# XMOS_TSBOARD_PHY.net
KiCad netlist of a schematic drawn in Altium Designer
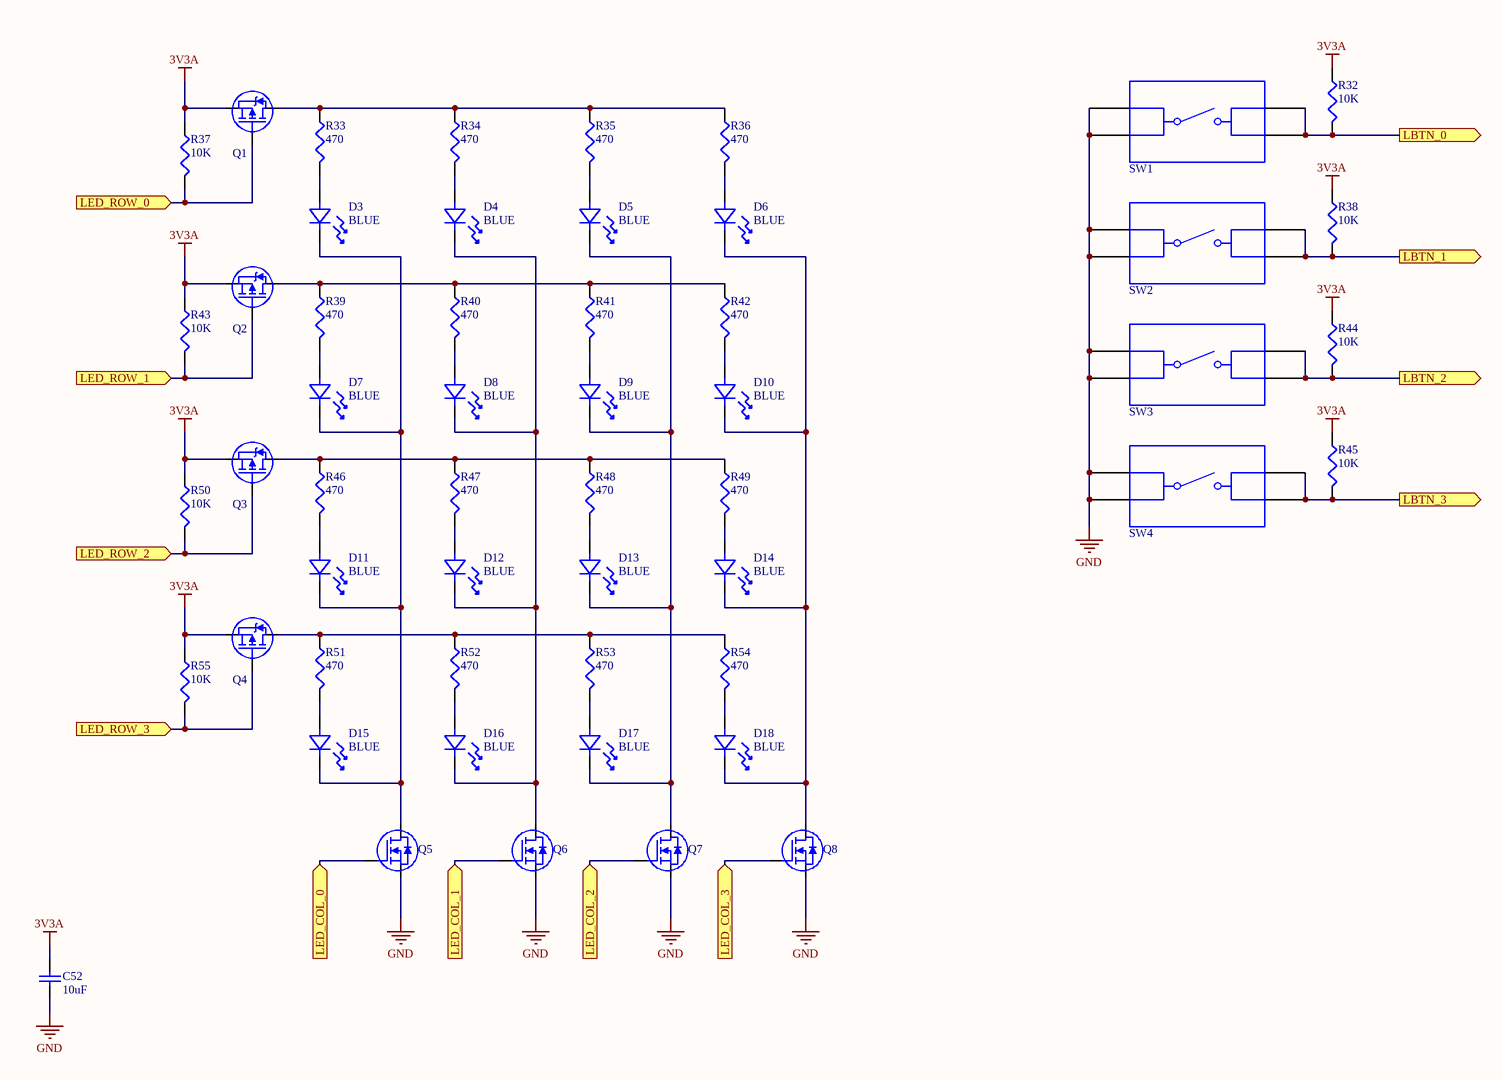
[diagram p0: XMOS_TSBOARD_PHY.SchDoc]

(export (version "E")
  (design (tool "Eeschema 10.0.6"))
  (components
    (comp (ref "C52")
      (value "10uF")
      (footprint "1608[0603]")
      (description "Capacitor (Semiconductor SIM Model)")
      (fields (field (name "Comment") "Cap Semi") (field (name "PUBLISHER") "Altium Limited"))
      (libsource (lib "Miscellaneous Devices") (part "Cap Semi"))
    )
    (comp (ref "D3")
      (value "BLUE")
      (footprint "0603_LED")
      (description "LED")
      (libsource (lib "Troposphere_lib") (part "LED"))
    )
    (comp (ref "D4")
      (value "BLUE")
      (footprint "0603_LED")
      (description "LED")
      (libsource (lib "Troposphere_lib") (part "LED"))
    )
    (comp (ref "D5")
      (value "BLUE")
      (footprint "0603_LED")
      (description "LED")
      (libsource (lib "Troposphere_lib") (part "LED"))
    )
    (comp (ref "D6")
      (value "BLUE")
      (footprint "0603_LED")
      (description "LED")
      (libsource (lib "Troposphere_lib") (part "LED"))
    )
    (comp (ref "D7")
      (value "BLUE")
      (footprint "0603_LED")
      (description "LED")
      (libsource (lib "Troposphere_lib") (part "LED"))
    )
    (comp (ref "D8")
      (value "BLUE")
      (footprint "0603_LED")
      (description "LED")
      (libsource (lib "Troposphere_lib") (part "LED"))
    )
    (comp (ref "D9")
      (value "BLUE")
      (footprint "0603_LED")
      (description "LED")
      (libsource (lib "Troposphere_lib") (part "LED"))
    )
    (comp (ref "D10")
      (value "BLUE")
      (footprint "0603_LED")
      (description "LED")
      (libsource (lib "Troposphere_lib") (part "LED"))
    )
    (comp (ref "D11")
      (value "BLUE")
      (footprint "0603_LED")
      (description "LED")
      (libsource (lib "Troposphere_lib") (part "LED"))
    )
    (comp (ref "D12")
      (value "BLUE")
      (footprint "0603_LED")
      (description "LED")
      (libsource (lib "Troposphere_lib") (part "LED"))
    )
    (comp (ref "D13")
      (value "BLUE")
      (footprint "0603_LED")
      (description "LED")
      (libsource (lib "Troposphere_lib") (part "LED"))
    )
    (comp (ref "D14")
      (value "BLUE")
      (footprint "0603_LED")
      (description "LED")
      (libsource (lib "Troposphere_lib") (part "LED"))
    )
    (comp (ref "D15")
      (value "BLUE")
      (footprint "0603_LED")
      (description "LED")
      (libsource (lib "Troposphere_lib") (part "LED"))
    )
    (comp (ref "D16")
      (value "BLUE")
      (footprint "0603_LED")
      (description "LED")
      (libsource (lib "Troposphere_lib") (part "LED"))
    )
    (comp (ref "D17")
      (value "BLUE")
      (footprint "0603_LED")
      (description "LED")
      (libsource (lib "Troposphere_lib") (part "LED"))
    )
    (comp (ref "D18")
      (value "BLUE")
      (footprint "0603_LED")
      (description "LED")
      (libsource (lib "Troposphere_lib") (part "LED"))
    )
    (comp (ref "Q1")
      (value "MOSFET")
      (footprint "SOT-23")
      (description "MOSFET, P-Channel, Logic Level, 50V, 130mA, SOT23")
      (libsource (lib "Troposphere_lib") (part "BSS84"))
    )
    (comp (ref "Q2")
      (value "MOSFET")
      (footprint "SOT-23")
      (description "MOSFET, P-Channel, Logic Level, 50V, 130mA, SOT23")
      (libsource (lib "Troposphere_lib") (part "BSS84"))
    )
    (comp (ref "Q3")
      (value "MOSFET")
      (footprint "SOT-23")
      (description "MOSFET, P-Channel, Logic Level, 50V, 130mA, SOT23")
      (libsource (lib "Troposphere_lib") (part "BSS84"))
    )
    (comp (ref "Q4")
      (value "MOSFET")
      (footprint "SOT-23")
      (description "MOSFET, P-Channel, Logic Level, 50V, 130mA, SOT23")
      (libsource (lib "Troposphere_lib") (part "BSS84"))
    )
    (comp (ref "Q5")
      (value "BSS138")
      (footprint "SOT-23")
      (description "MOSFET, N-Channel, Logic Level, 50V, 220mA, SOT23")
      (libsource (lib "Troposphere_lib") (part "BSS138"))
    )
    (comp (ref "Q6")
      (value "BSS138")
      (footprint "SOT-23")
      (description "MOSFET, N-Channel, Logic Level, 50V, 220mA, SOT23")
      (libsource (lib "Troposphere_lib") (part "BSS138"))
    )
    (comp (ref "Q7")
      (value "BSS138")
      (footprint "SOT-23")
      (description "MOSFET, N-Channel, Logic Level, 50V, 220mA, SOT23")
      (libsource (lib "Troposphere_lib") (part "BSS138"))
    )
    (comp (ref "Q8")
      (value "BSS138")
      (footprint "SOT-23")
      (description "MOSFET, N-Channel, Logic Level, 50V, 220mA, SOT23")
      (libsource (lib "Troposphere_lib") (part "BSS138"))
    )
    (comp (ref "R32")
      (value "10K")
      (footprint "J1-0603")
      (description "Resistor")
      (fields (field (name "Comment") "Res3") (field (name "PUBLISHER") "Altium Limited"))
      (libsource (lib "Miscellaneous Devices") (part "Res3"))
    )
    (comp (ref "R33")
      (value "470")
      (footprint "J1-0603")
      (description "Resistor")
      (fields (field (name "Comment") "Res3") (field (name "PUBLISHER") "Altium Limited"))
      (libsource (lib "Miscellaneous Devices") (part "Res3"))
    )
    (comp (ref "R34")
      (value "470")
      (footprint "J1-0603")
      (description "Resistor")
      (fields (field (name "Comment") "Res3") (field (name "PUBLISHER") "Altium Limited"))
      (libsource (lib "Miscellaneous Devices") (part "Res3"))
    )
    (comp (ref "R35")
      (value "470")
      (footprint "J1-0603")
      (description "Resistor")
      (fields (field (name "Comment") "Res3") (field (name "PUBLISHER") "Altium Limited"))
      (libsource (lib "Miscellaneous Devices") (part "Res3"))
    )
    (comp (ref "R36")
      (value "470")
      (footprint "J1-0603")
      (description "Resistor")
      (fields (field (name "Comment") "Res3") (field (name "PUBLISHER") "Altium Limited"))
      (libsource (lib "Miscellaneous Devices") (part "Res3"))
    )
    (comp (ref "R37")
      (value "10K")
      (footprint "J1-0603")
      (description "Resistor")
      (fields (field (name "Comment") "Res3") (field (name "PUBLISHER") "Altium Limited"))
      (libsource (lib "Miscellaneous Devices") (part "Res3"))
    )
    (comp (ref "R38")
      (value "10K")
      (footprint "J1-0603")
      (description "Resistor")
      (fields (field (name "Comment") "Res3") (field (name "PUBLISHER") "Altium Limited"))
      (libsource (lib "Miscellaneous Devices") (part "Res3"))
    )
    (comp (ref "R39")
      (value "470")
      (footprint "J1-0603")
      (description "Resistor")
      (fields (field (name "Comment") "Res3") (field (name "PUBLISHER") "Altium Limited"))
      (libsource (lib "Miscellaneous Devices") (part "Res3"))
    )
    (comp (ref "R40")
      (value "470")
      (footprint "J1-0603")
      (description "Resistor")
      (fields (field (name "Comment") "Res3") (field (name "PUBLISHER") "Altium Limited"))
      (libsource (lib "Miscellaneous Devices") (part "Res3"))
    )
    (comp (ref "R41")
      (value "470")
      (footprint "J1-0603")
      (description "Resistor")
      (fields (field (name "Comment") "Res3") (field (name "PUBLISHER") "Altium Limited"))
      (libsource (lib "Miscellaneous Devices") (part "Res3"))
    )
    (comp (ref "R42")
      (value "470")
      (footprint "J1-0603")
      (description "Resistor")
      (fields (field (name "Comment") "Res3") (field (name "PUBLISHER") "Altium Limited"))
      (libsource (lib "Miscellaneous Devices") (part "Res3"))
    )
    (comp (ref "R43")
      (value "10K")
      (footprint "J1-0603")
      (description "Resistor")
      (fields (field (name "Comment") "Res3") (field (name "PUBLISHER") "Altium Limited"))
      (libsource (lib "Miscellaneous Devices") (part "Res3"))
    )
    (comp (ref "R44")
      (value "10K")
      (footprint "J1-0603")
      (description "Resistor")
      (fields (field (name "Comment") "Res3") (field (name "PUBLISHER") "Altium Limited"))
      (libsource (lib "Miscellaneous Devices") (part "Res3"))
    )
    (comp (ref "R45")
      (value "10K")
      (footprint "J1-0603")
      (description "Resistor")
      (fields (field (name "Comment") "Res3") (field (name "PUBLISHER") "Altium Limited"))
      (libsource (lib "Miscellaneous Devices") (part "Res3"))
    )
    (comp (ref "R46")
      (value "470")
      (footprint "J1-0603")
      (description "Resistor")
      (fields (field (name "Comment") "Res3") (field (name "PUBLISHER") "Altium Limited"))
      (libsource (lib "Miscellaneous Devices") (part "Res3"))
    )
    (comp (ref "R47")
      (value "470")
      (footprint "J1-0603")
      (description "Resistor")
      (fields (field (name "Comment") "Res3") (field (name "PUBLISHER") "Altium Limited"))
      (libsource (lib "Miscellaneous Devices") (part "Res3"))
    )
    (comp (ref "R48")
      (value "470")
      (footprint "J1-0603")
      (description "Resistor")
      (fields (field (name "Comment") "Res3") (field (name "PUBLISHER") "Altium Limited"))
      (libsource (lib "Miscellaneous Devices") (part "Res3"))
    )
    (comp (ref "R49")
      (value "470")
      (footprint "J1-0603")
      (description "Resistor")
      (fields (field (name "Comment") "Res3") (field (name "PUBLISHER") "Altium Limited"))
      (libsource (lib "Miscellaneous Devices") (part "Res3"))
    )
    (comp (ref "R50")
      (value "10K")
      (footprint "J1-0603")
      (description "Resistor")
      (fields (field (name "Comment") "Res3") (field (name "PUBLISHER") "Altium Limited"))
      (libsource (lib "Miscellaneous Devices") (part "Res3"))
    )
    (comp (ref "R51")
      (value "470")
      (footprint "J1-0603")
      (description "Resistor")
      (fields (field (name "Comment") "Res3") (field (name "PUBLISHER") "Altium Limited"))
      (libsource (lib "Miscellaneous Devices") (part "Res3"))
    )
    (comp (ref "R52")
      (value "470")
      (footprint "J1-0603")
      (description "Resistor")
      (fields (field (name "Comment") "Res3") (field (name "PUBLISHER") "Altium Limited"))
      (libsource (lib "Miscellaneous Devices") (part "Res3"))
    )
    (comp (ref "R53")
      (value "470")
      (footprint "J1-0603")
      (description "Resistor")
      (fields (field (name "Comment") "Res3") (field (name "PUBLISHER") "Altium Limited"))
      (libsource (lib "Miscellaneous Devices") (part "Res3"))
    )
    (comp (ref "R54")
      (value "470")
      (footprint "J1-0603")
      (description "Resistor")
      (fields (field (name "Comment") "Res3") (field (name "PUBLISHER") "Altium Limited"))
      (libsource (lib "Miscellaneous Devices") (part "Res3"))
    )
    (comp (ref "R55")
      (value "10K")
      (footprint "J1-0603")
      (description "Resistor")
      (fields (field (name "Comment") "Res3") (field (name "PUBLISHER") "Altium Limited"))
      (libsource (lib "Miscellaneous Devices") (part "Res3"))
    )
    (comp (ref "SW1")
      (value "FSM6JSMA")
      (footprint "SW_6x6")
      (description "Switch Push Button N.O. SPST Round Button 0.05A 12VDC 1VA Alternate Contact Gull Wing SMD T/R")
      (libsource (lib "Troposphere_lib") (part "FSM6JSMA"))
    )
    (comp (ref "SW2")
      (value "FSM6JSMA")
      (footprint "SW_6x6")
      (description "Switch Push Button N.O. SPST Round Button 0.05A 12VDC 1VA Alternate Contact Gull Wing SMD T/R")
      (libsource (lib "Troposphere_lib") (part "FSM6JSMA"))
    )
    (comp (ref "SW3")
      (value "FSM6JSMA")
      (footprint "SW_6x6")
      (description "Switch Push Button N.O. SPST Round Button 0.05A 12VDC 1VA Alternate Contact Gull Wing SMD T/R")
      (libsource (lib "Troposphere_lib") (part "FSM6JSMA"))
    )
    (comp (ref "SW4")
      (value "FSM6JSMA")
      (footprint "SW_6x6")
      (description "Switch Push Button N.O. SPST Round Button 0.05A 12VDC 1VA Alternate Contact Gull Wing SMD T/R")
      (libsource (lib "Troposphere_lib") (part "FSM6JSMA"))
    )
  )
  (nets
    (net (code "1") (name "/LBTN_0") (class "Default")
      (node (ref "R32") (pin "2") (pinfunction "2_2") (pintype "passive"))
      (node (ref "SW1") (pin "3") (pinfunction "3_3") (pintype "passive"))
      (node (ref "SW1") (pin "4") (pinfunction "4_4") (pintype "passive"))
    )
    (net (code "2") (name "/LBTN_1") (class "Default")
      (node (ref "R38") (pin "2") (pinfunction "2_2") (pintype "passive"))
      (node (ref "SW2") (pin "3") (pinfunction "3_3") (pintype "passive"))
      (node (ref "SW2") (pin "4") (pinfunction "4_4") (pintype "passive"))
    )
    (net (code "3") (name "/LBTN_2") (class "Default")
      (node (ref "R44") (pin "2") (pinfunction "2_2") (pintype "passive"))
      (node (ref "SW3") (pin "3") (pinfunction "3_3") (pintype "passive"))
      (node (ref "SW3") (pin "4") (pinfunction "4_4") (pintype "passive"))
    )
    (net (code "4") (name "/LBTN_3") (class "Default")
      (node (ref "R45") (pin "2") (pinfunction "2_2") (pintype "passive"))
      (node (ref "SW4") (pin "3") (pinfunction "3_3") (pintype "passive"))
      (node (ref "SW4") (pin "4") (pinfunction "4_4") (pintype "passive"))
    )
    (net (code "5") (name "/LED_COL_0") (class "Default")
      (node (ref "Q5") (pin "1") (pinfunction "G_1") (pintype "passive"))
    )
    (net (code "6") (name "/LED_COL_1") (class "Default")
      (node (ref "Q6") (pin "1") (pinfunction "G_1") (pintype "passive"))
    )
    (net (code "7") (name "/LED_COL_2") (class "Default")
      (node (ref "Q7") (pin "1") (pinfunction "G_1") (pintype "passive"))
    )
    (net (code "8") (name "/LED_COL_3") (class "Default")
      (node (ref "Q8") (pin "1") (pinfunction "G_1") (pintype "passive"))
    )
    (net (code "9") (name "/LED_ROW_0") (class "Default")
      (node (ref "Q1") (pin "1") (pinfunction "G_1") (pintype "passive"))
      (node (ref "R37") (pin "2") (pinfunction "2_2") (pintype "passive"))
    )
    (net (code "10") (name "/LED_ROW_1") (class "Default")
      (node (ref "Q2") (pin "1") (pinfunction "G_1") (pintype "passive"))
      (node (ref "R43") (pin "2") (pinfunction "2_2") (pintype "passive"))
    )
    (net (code "11") (name "/LED_ROW_2") (class "Default")
      (node (ref "Q3") (pin "1") (pinfunction "G_1") (pintype "passive"))
      (node (ref "R50") (pin "2") (pinfunction "2_2") (pintype "passive"))
    )
    (net (code "12") (name "/LED_ROW_3") (class "Default")
      (node (ref "Q4") (pin "1") (pinfunction "G_1") (pintype "passive"))
      (node (ref "R55") (pin "2") (pinfunction "2_2") (pintype "passive"))
    )
    (net (code "13") (name "3V3A") (class "Default")
      (node (ref "C52") (pin "2") (pinfunction "2_2") (pintype "passive"))
      (node (ref "Q1") (pin "2") (pinfunction "S_2") (pintype "passive"))
      (node (ref "Q2") (pin "2") (pinfunction "S_2") (pintype "passive"))
      (node (ref "Q3") (pin "2") (pinfunction "S_2") (pintype "passive"))
      (node (ref "Q4") (pin "2") (pinfunction "S_2") (pintype "passive"))
      (node (ref "R32") (pin "1") (pinfunction "1_1") (pintype "passive"))
      (node (ref "R37") (pin "1") (pinfunction "1_1") (pintype "passive"))
      (node (ref "R38") (pin "1") (pinfunction "1_1") (pintype "passive"))
      (node (ref "R43") (pin "1") (pinfunction "1_1") (pintype "passive"))
      (node (ref "R44") (pin "1") (pinfunction "1_1") (pintype "passive"))
      (node (ref "R45") (pin "1") (pinfunction "1_1") (pintype "passive"))
      (node (ref "R50") (pin "1") (pinfunction "1_1") (pintype "passive"))
      (node (ref "R55") (pin "1") (pinfunction "1_1") (pintype "passive"))
    )
    (net (code "14") (name "GND") (class "Default")
      (node (ref "C52") (pin "1") (pinfunction "1_1") (pintype "passive"))
      (node (ref "Q5") (pin "2") (pinfunction "S_2") (pintype "passive"))
      (node (ref "Q6") (pin "2") (pinfunction "S_2") (pintype "passive"))
      (node (ref "Q7") (pin "2") (pinfunction "S_2") (pintype "passive"))
      (node (ref "Q8") (pin "2") (pinfunction "S_2") (pintype "passive"))
      (node (ref "SW1") (pin "1") (pinfunction "1_1") (pintype "passive"))
      (node (ref "SW1") (pin "2") (pinfunction "2_2") (pintype "passive"))
      (node (ref "SW2") (pin "1") (pinfunction "1_1") (pintype "passive"))
      (node (ref "SW2") (pin "2") (pinfunction "2_2") (pintype "passive"))
      (node (ref "SW3") (pin "1") (pinfunction "1_1") (pintype "passive"))
      (node (ref "SW3") (pin "2") (pinfunction "2_2") (pintype "passive"))
      (node (ref "SW4") (pin "1") (pinfunction "1_1") (pintype "passive"))
      (node (ref "SW4") (pin "2") (pinfunction "2_2") (pintype "passive"))
    )
    (net (code "15") (name "Net-(D3-Pad2)") (class "Default")
      (node (ref "D3") (pin "2") (pinfunction "2_2") (pintype "passive"))
      (node (ref "R33") (pin "2") (pinfunction "2_2") (pintype "passive"))
    )
    (net (code "16") (name "Net-(D4-Pad2)") (class "Default")
      (node (ref "D4") (pin "2") (pinfunction "2_2") (pintype "passive"))
      (node (ref "R34") (pin "2") (pinfunction "2_2") (pintype "passive"))
    )
    (net (code "17") (name "Net-(D5-Pad2)") (class "Default")
      (node (ref "D5") (pin "2") (pinfunction "2_2") (pintype "passive"))
      (node (ref "R35") (pin "2") (pinfunction "2_2") (pintype "passive"))
    )
    (net (code "18") (name "Net-(D6-Pad2)") (class "Default")
      (node (ref "D6") (pin "2") (pinfunction "2_2") (pintype "passive"))
      (node (ref "R36") (pin "2") (pinfunction "2_2") (pintype "passive"))
    )
    (net (code "19") (name "Net-(D7-Pad2)") (class "Default")
      (node (ref "D7") (pin "2") (pinfunction "2_2") (pintype "passive"))
      (node (ref "R39") (pin "2") (pinfunction "2_2") (pintype "passive"))
    )
    (net (code "20") (name "Net-(D8-Pad2)") (class "Default")
      (node (ref "D8") (pin "2") (pinfunction "2_2") (pintype "passive"))
      (node (ref "R40") (pin "2") (pinfunction "2_2") (pintype "passive"))
    )
    (net (code "21") (name "Net-(D9-Pad2)") (class "Default")
      (node (ref "D9") (pin "2") (pinfunction "2_2") (pintype "passive"))
      (node (ref "R41") (pin "2") (pinfunction "2_2") (pintype "passive"))
    )
    (net (code "22") (name "Net-(D10-Pad2)") (class "Default")
      (node (ref "D10") (pin "2") (pinfunction "2_2") (pintype "passive"))
      (node (ref "R42") (pin "2") (pinfunction "2_2") (pintype "passive"))
    )
    (net (code "23") (name "Net-(D11-Pad2)") (class "Default")
      (node (ref "D11") (pin "2") (pinfunction "2_2") (pintype "passive"))
      (node (ref "R46") (pin "2") (pinfunction "2_2") (pintype "passive"))
    )
    (net (code "24") (name "Net-(D12-Pad2)") (class "Default")
      (node (ref "D12") (pin "2") (pinfunction "2_2") (pintype "passive"))
      (node (ref "R47") (pin "2") (pinfunction "2_2") (pintype "passive"))
    )
    (net (code "25") (name "Net-(D13-Pad2)") (class "Default")
      (node (ref "D13") (pin "2") (pinfunction "2_2") (pintype "passive"))
      (node (ref "R48") (pin "2") (pinfunction "2_2") (pintype "passive"))
    )
    (net (code "26") (name "Net-(D14-Pad2)") (class "Default")
      (node (ref "D14") (pin "2") (pinfunction "2_2") (pintype "passive"))
      (node (ref "R49") (pin "2") (pinfunction "2_2") (pintype "passive"))
    )
    (net (code "27") (name "Net-(D15-Pad2)") (class "Default")
      (node (ref "D15") (pin "2") (pinfunction "2_2") (pintype "passive"))
      (node (ref "R51") (pin "2") (pinfunction "2_2") (pintype "passive"))
    )
    (net (code "28") (name "Net-(D16-Pad2)") (class "Default")
      (node (ref "D16") (pin "2") (pinfunction "2_2") (pintype "passive"))
      (node (ref "R52") (pin "2") (pinfunction "2_2") (pintype "passive"))
    )
    (net (code "29") (name "Net-(D17-Pad2)") (class "Default")
      (node (ref "D17") (pin "2") (pinfunction "2_2") (pintype "passive"))
      (node (ref "R53") (pin "2") (pinfunction "2_2") (pintype "passive"))
    )
    (net (code "30") (name "Net-(D18-Pad2)") (class "Default")
      (node (ref "D18") (pin "2") (pinfunction "2_2") (pintype "passive"))
      (node (ref "R54") (pin "2") (pinfunction "2_2") (pintype "passive"))
    )
    (net (code "31") (name "Net-(Q1-D)") (class "Default")
      (node (ref "Q1") (pin "3") (pinfunction "D_3") (pintype "passive"))
      (node (ref "R33") (pin "1") (pinfunction "1_1") (pintype "passive"))
      (node (ref "R34") (pin "1") (pinfunction "1_1") (pintype "passive"))
      (node (ref "R35") (pin "1") (pinfunction "1_1") (pintype "passive"))
      (node (ref "R36") (pin "1") (pinfunction "1_1") (pintype "passive"))
    )
    (net (code "32") (name "Net-(Q2-D)") (class "Default")
      (node (ref "Q2") (pin "3") (pinfunction "D_3") (pintype "passive"))
      (node (ref "R39") (pin "1") (pinfunction "1_1") (pintype "passive"))
      (node (ref "R40") (pin "1") (pinfunction "1_1") (pintype "passive"))
      (node (ref "R41") (pin "1") (pinfunction "1_1") (pintype "passive"))
      (node (ref "R42") (pin "1") (pinfunction "1_1") (pintype "passive"))
    )
    (net (code "33") (name "Net-(Q3-D)") (class "Default")
      (node (ref "Q3") (pin "3") (pinfunction "D_3") (pintype "passive"))
      (node (ref "R46") (pin "1") (pinfunction "1_1") (pintype "passive"))
      (node (ref "R47") (pin "1") (pinfunction "1_1") (pintype "passive"))
      (node (ref "R48") (pin "1") (pinfunction "1_1") (pintype "passive"))
      (node (ref "R49") (pin "1") (pinfunction "1_1") (pintype "passive"))
    )
    (net (code "34") (name "Net-(Q4-D)") (class "Default")
      (node (ref "Q4") (pin "3") (pinfunction "D_3") (pintype "passive"))
      (node (ref "R51") (pin "1") (pinfunction "1_1") (pintype "passive"))
      (node (ref "R52") (pin "1") (pinfunction "1_1") (pintype "passive"))
      (node (ref "R53") (pin "1") (pinfunction "1_1") (pintype "passive"))
      (node (ref "R54") (pin "1") (pinfunction "1_1") (pintype "passive"))
    )
    (net (code "35") (name "Net-(Q5-D)") (class "Default")
      (node (ref "D11") (pin "1") (pinfunction "1_1") (pintype "passive"))
      (node (ref "D15") (pin "1") (pinfunction "1_1") (pintype "passive"))
      (node (ref "D3") (pin "1") (pinfunction "1_1") (pintype "passive"))
      (node (ref "D7") (pin "1") (pinfunction "1_1") (pintype "passive"))
      (node (ref "Q5") (pin "3") (pinfunction "D_3") (pintype "passive"))
    )
    (net (code "36") (name "Net-(Q6-D)") (class "Default")
      (node (ref "D12") (pin "1") (pinfunction "1_1") (pintype "passive"))
      (node (ref "D16") (pin "1") (pinfunction "1_1") (pintype "passive"))
      (node (ref "D4") (pin "1") (pinfunction "1_1") (pintype "passive"))
      (node (ref "D8") (pin "1") (pinfunction "1_1") (pintype "passive"))
      (node (ref "Q6") (pin "3") (pinfunction "D_3") (pintype "passive"))
    )
    (net (code "37") (name "Net-(Q7-D)") (class "Default")
      (node (ref "D13") (pin "1") (pinfunction "1_1") (pintype "passive"))
      (node (ref "D17") (pin "1") (pinfunction "1_1") (pintype "passive"))
      (node (ref "D5") (pin "1") (pinfunction "1_1") (pintype "passive"))
      (node (ref "D9") (pin "1") (pinfunction "1_1") (pintype "passive"))
      (node (ref "Q7") (pin "3") (pinfunction "D_3") (pintype "passive"))
    )
    (net (code "38") (name "Net-(Q8-D)") (class "Default")
      (node (ref "D10") (pin "1") (pinfunction "1_1") (pintype "passive"))
      (node (ref "D14") (pin "1") (pinfunction "1_1") (pintype "passive"))
      (node (ref "D18") (pin "1") (pinfunction "1_1") (pintype "passive"))
      (node (ref "D6") (pin "1") (pinfunction "1_1") (pintype "passive"))
      (node (ref "Q8") (pin "3") (pinfunction "D_3") (pintype "passive"))
    )
  )
)
